# Sheet1.net
KiCad netlist of a schematic drawn in Altium Designer
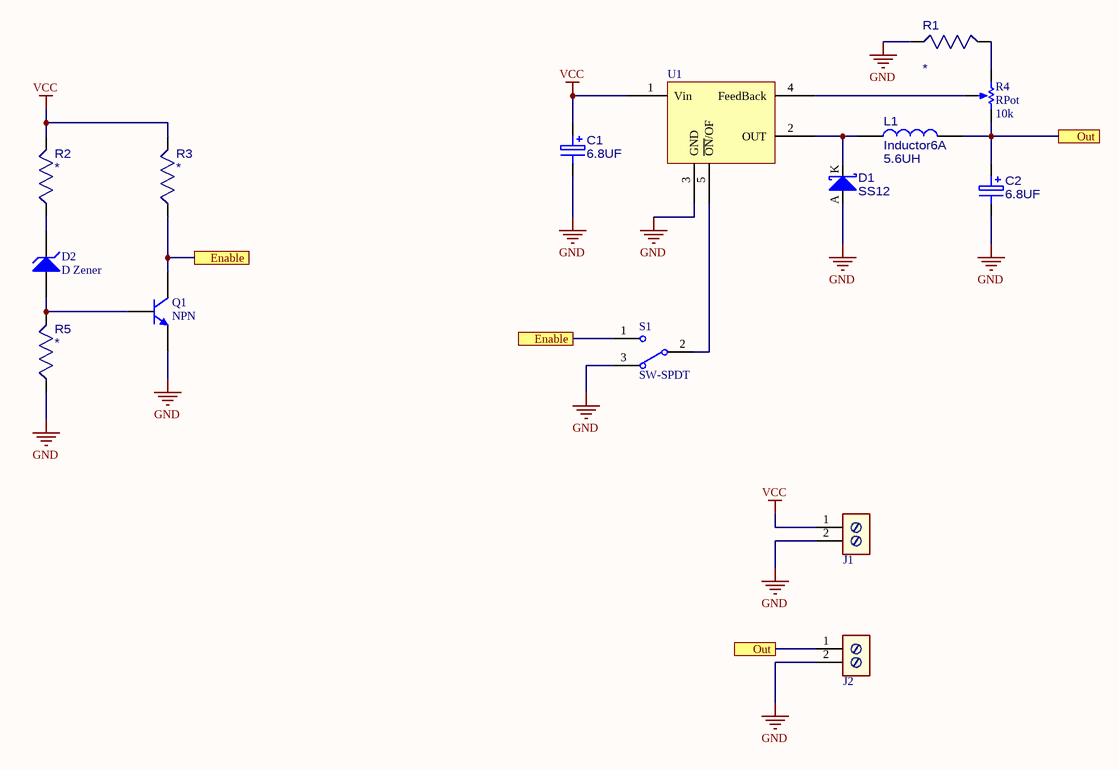
[diagram p0: Sheet1.SchDoc]

(export (version "E")
  (design (tool "Eeschema 10.0.6"))
  (components
    (comp (ref "C1")
      (value "6.8UF")
      (footprint "RADPOL8X11")
      (libsource (lib "i9Library_v1.7.5") (part "ELECTRO1_1"))
    )
    (comp (ref "C2")
      (value "6.8UF")
      (footprint "RADPOL8X11")
      (libsource (lib "i9Library_v1.7.5") (part "ELECTRO1_1"))
    )
    (comp (ref "D1")
      (value "SS12")
      (footprint "DIO_PTH_5MM")
      (description "Schottky Diode")
      (fields
        (field (name "DIGIKEY PART NUMBER") "SS12E-TPMSCT-ND")
        (field (name "Comment") "DIODE - SCHOTTKY")
      )
      (libsource (lib "i9Library_v1.7.5") (part "DIODE - SCHOTTKY"))
    )
    (comp (ref "D2")
      (value "D Zener")
      (footprint "DIODE-0.7")
      (description "Zener Diode")
      (fields (field (name "PUBLISHER") "Altium Limited"))
      (libsource (lib "Miscellaneous Devices") (part "D Zener"))
    )
    (comp (ref "J1")
      (value "2-Ways Wire-to-Board Horizontal")
      (footprint "KF128 2P")
      (description "2 Position Wire to Board Terminal Block Horizontal with Board 0.200\" (5.08mm) Through Hole")
      (libsource (lib "Connectors") (part "KF128 2P"))
    )
    (comp (ref "J2")
      (value "2-Ways Wire-to-Board Horizontal")
      (footprint "KF128 2P")
      (description "2 Position Wire to Board Terminal Block Horizontal with Board 0.200\" (5.08mm) Through Hole")
      (libsource (lib "Connectors") (part "KF128 2P"))
    )
    (comp (ref "L1")
      (value "5.6UH")
      (footprint "Inductor6A")
      (description "FIXED IND 5.6UH 6A 14.4 MOHM SMD")
      (libsource (lib "i9Library_v1.7.5") (part "IND_1"))
    )
    (comp (ref "Q1")
      (value "NPN")
      (footprint "TO-226-AA")
      (description "NPN Bipolar Transistor")
      (fields (field (name "PUBLISHER") "Altium Limited"))
      (libsource (lib "Miscellaneous Devices") (part "NPN"))
    )
    (comp (ref "R1")
      (value "*")
      (footprint "RES-7.62mm")
      (description "Pin Through Hole Resistor 300mils/7.62mm")
      (fields (field (name "ALTIUM_VALUE") "*"))
      (libsource (lib "i9Library_v1.7.5") (part "RES_PTH300"))
    )
    (comp (ref "R2")
      (value "*")
      (footprint "RES-7.62mm")
      (description "Pin Through Hole Resistor 300mils/7.62mm")
      (fields (field (name "ALTIUM_VALUE") "*"))
      (libsource (lib "i9Library_v1.7.5") (part "RES_PTH300"))
    )
    (comp (ref "R3")
      (value "*")
      (footprint "RES-7.62mm")
      (description "Pin Through Hole Resistor 300mils/7.62mm")
      (fields (field (name "ALTIUM_VALUE") "*"))
      (libsource (lib "i9Library_v1.7.5") (part "RES_PTH300"))
    )
    (comp (ref "R4")
      (value "RPot")
      (footprint "VR5")
      (description "Potentiometer")
      (fields (field (name "ALTIUM_VALUE") "10k") (field (name "PUBLISHER") "Altium Limited"))
      (libsource (lib "Miscellaneous Devices") (part "RPot"))
    )
    (comp (ref "R5")
      (value "*")
      (footprint "RES-7.62mm")
      (description "Pin Through Hole Resistor 300mils/7.62mm")
      (fields (field (name "ALTIUM_VALUE") "*"))
      (libsource (lib "i9Library_v1.7.5") (part "RES_PTH300"))
    )
    (comp (ref "S1")
      (value "SW-SPDT")
      (footprint "Pin Header 3 Ways")
      (description "SPDT Subminiature Toggle Switch, Right Angle Mounting, Vertical Actuation")
      (fields (field (name "PUBLISHER") "Altium Limited"))
      (libsource (lib "Miscellaneous Devices") (part "SW-SPDT"))
    )
    (comp (ref "U1")
      (value "LM2576HV 5.0")
      (footprint "LM2576-TO220")
      (libsource (lib "i9Library_v1.7.5") (part "LM2576"))
    )
  )
  (nets
    (net (code "1") (name "/Enable") (class "Default")
      (node (ref "Q1") (pin "1") (pinfunction "C_1") (pintype "passive"))
      (node (ref "R3") (pin "1") (pintype "passive"))
      (node (ref "S1") (pin "1") (pinfunction "1_1") (pintype "passive"))
    )
    (net (code "2") (name "/Out") (class "Default")
      (node (ref "C2") (pin "1") (pintype "passive"))
      (node (ref "J2") (pin "1") (pinfunction "1_1") (pintype "passive"))
      (node (ref "L1") (pin "2") (pinfunction "2_2") (pintype "passive"))
      (node (ref "R4") (pin "2") (pinfunction "BOT_2") (pintype "passive"))
    )
    (net (code "3") (name "GND") (class "Default")
      (node (ref "C1") (pin "2") (pintype "passive"))
      (node (ref "C2") (pin "2") (pintype "passive"))
      (node (ref "D1") (pin "A") (pinfunction "A_A") (pintype "passive"))
      (node (ref "J1") (pin "2") (pinfunction "2_2") (pintype "passive"))
      (node (ref "J2") (pin "2") (pinfunction "2_2") (pintype "passive"))
      (node (ref "Q1") (pin "3") (pinfunction "E_3") (pintype "passive"))
      (node (ref "R1") (pin "1") (pintype "passive"))
      (node (ref "R5") (pin "1") (pintype "passive"))
      (node (ref "S1") (pin "3") (pinfunction "3_3") (pintype "passive"))
      (node (ref "U1") (pin "3") (pinfunction "GND_3") (pintype "passive"))
    )
    (net (code "4") (name "Net-(D2-A)") (class "Default")
      (node (ref "D2") (pin "1") (pinfunction "A_1") (pintype "passive"))
      (node (ref "Q1") (pin "2") (pinfunction "B_2") (pintype "passive"))
      (node (ref "R5") (pin "2") (pintype "passive"))
    )
    (net (code "5") (name "Net-(D2-K)") (class "Default")
      (node (ref "D2") (pin "2") (pinfunction "K_2") (pintype "passive"))
      (node (ref "R2") (pin "1") (pintype "passive"))
    )
    (net (code "6") (name "Net-(R4-TAP)") (class "Default")
      (node (ref "R4") (pin "3") (pinfunction "TAP_3") (pintype "passive"))
      (node (ref "U1") (pin "4") (pinfunction "FeedBack_4") (pintype "passive"))
    )
    (net (code "7") (name "Net-(R4-TOP)") (class "Default")
      (node (ref "R1") (pin "2") (pintype "passive"))
      (node (ref "R4") (pin "1") (pinfunction "TOP_1") (pintype "passive"))
    )
    (net (code "8") (name "Net-(U1-OUT)") (class "Default")
      (node (ref "D1") (pin "K") (pinfunction "K_K") (pintype "passive"))
      (node (ref "L1") (pin "1") (pinfunction "1_1") (pintype "passive"))
      (node (ref "U1") (pin "2") (pinfunction "OUT_2") (pintype "passive"))
    )
    (net (code "9") (name "Net-(U1-~{ON}{slash}OF)") (class "Default")
      (node (ref "S1") (pin "2") (pinfunction "2_2") (pintype "passive"))
      (node (ref "U1") (pin "5") (pinfunction "~{ON}/OF_5") (pintype "passive"))
    )
    (net (code "10") (name "VCC") (class "Default")
      (node (ref "C1") (pin "1") (pintype "passive"))
      (node (ref "J1") (pin "1") (pinfunction "1_1") (pintype "passive"))
      (node (ref "R2") (pin "2") (pintype "passive"))
      (node (ref "R3") (pin "2") (pintype "passive"))
      (node (ref "U1") (pin "1") (pinfunction "Vin_1") (pintype "passive"))
    )
  )
)
